# EntradaSensorTemperatura.net
KiCad netlist of a schematic drawn in Altium Designer
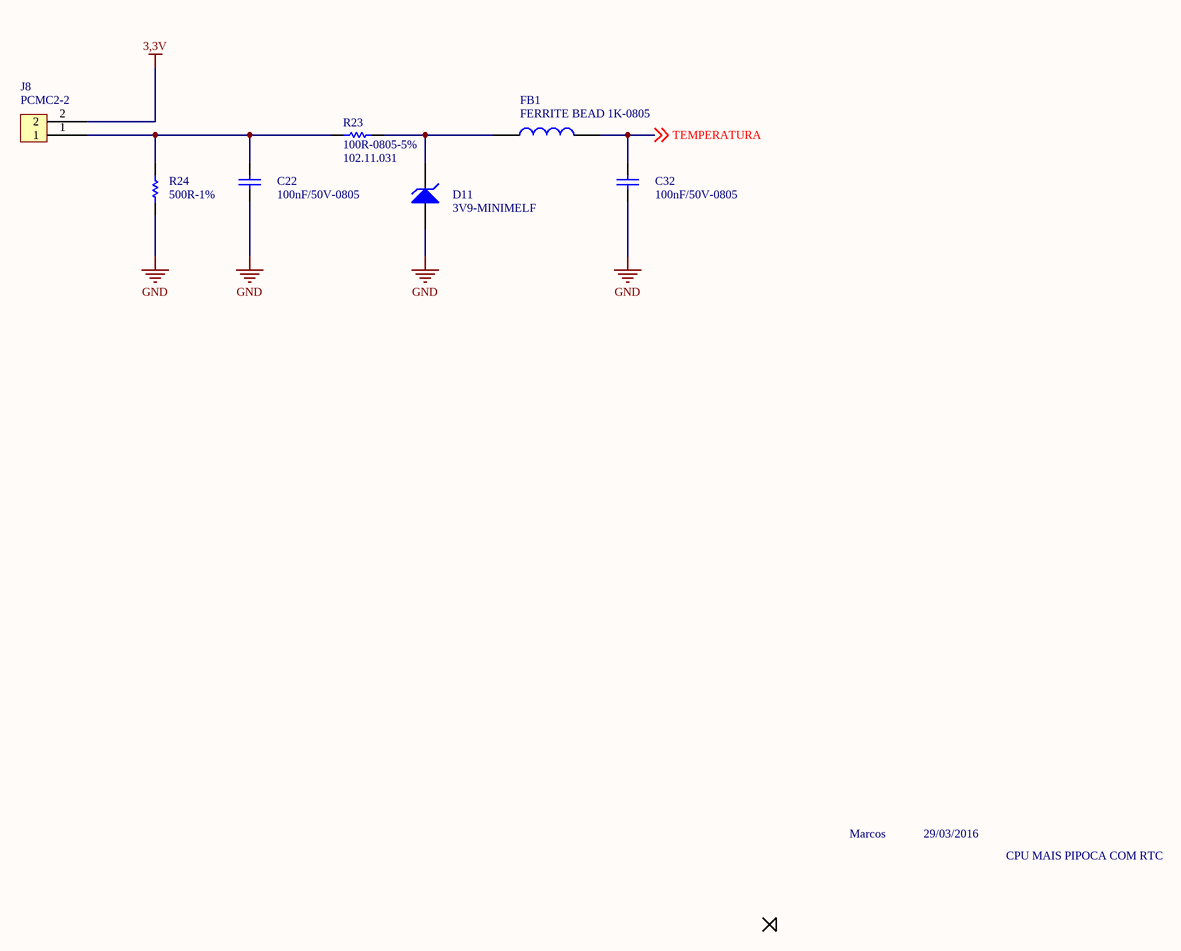
[diagram p0: EntradaSensorTemperatura.SchDoc]

(export (version "E")
  (design (tool "Eeschema 10.0.6"))
  (components
    (comp (ref "C22")
      (value "100nF/50V-0805")
      (footprint "0805-REVISADO O")
      (description "100nF/50-0805-NPO")
      (libsource (lib "AquinoLib") (part "100nF/50-0805-NPO"))
    )
    (comp (ref "C32")
      (value "100nF/50V-0805")
      (footprint "0805-REVISADO O")
      (description "100nF/50-0805-NPO")
      (libsource (lib "AquinoLib") (part "100nF/50-0805-NPO"))
    )
    (comp (ref "D11")
      (value "3V9-MINIMELF")
      (footprint "MINIMLEF/SOD80")
      (description "3V3-SOD80-1/2W")
      (libsource (lib "AquinoLib") (part "ZENER 3V3-SOD80"))
    )
    (comp (ref "FB1")
      (value "FERRITE BEAD 1K-0805")
      (footprint "0805-REVISADO O")
      (libsource (lib "AquinoLib") (part "FERRITE BEAD 1K-0805"))
    )
    (comp (ref "J8") (value "PCMC2-2") (footprint "PCMC2-2") (libsource (lib "AquinoLib") (part "PCMC2-2")))
    (comp (ref "R23")
      (value "100R-0805-5%")
      (footprint "0805-REVISADO O")
      (fields (field (name "ERP") "102.11.031"))
      (libsource (lib "AquinoLib") (part "100R-0805-5%"))
    )
    (comp (ref "R24")
      (value "500R-1%")
      (footprint "0805-REVISADO O")
      (description "10K-0805-5%")
      (libsource (lib "AquinoLib") (part "10K-0805-5%"))
    )
  )
  (nets
    (net (code "1") (name "3,3V") (class "Default")
      (node (ref "J8") (pin "2") (pinfunction "2_2") (pintype "passive"))
    )
    (net (code "2") (name "GND") (class "Default")
      (node (ref "C22") (pin "1") (pinfunction "1_1") (pintype "passive"))
      (node (ref "C32") (pin "1") (pinfunction "1_1") (pintype "passive"))
      (node (ref "D11") (pin "1") (pinfunction "A_1") (pintype "passive"))
      (node (ref "R24") (pin "1") (pinfunction "1_1") (pintype "passive"))
    )
    (net (code "3") (name "Net-(C22-Pad2)") (class "Default")
      (node (ref "C22") (pin "2") (pinfunction "2_2") (pintype "passive"))
      (node (ref "J8") (pin "1") (pinfunction "1_1") (pintype "passive"))
      (node (ref "R23") (pin "1") (pinfunction "1_1") (pintype "passive"))
      (node (ref "R24") (pin "2") (pinfunction "2_2") (pintype "passive"))
    )
    (net (code "4") (name "Net-(D11-K)") (class "Default")
      (node (ref "D11") (pin "2") (pinfunction "K_2") (pintype "passive"))
      (node (ref "FB1") (pin "1") (pinfunction "1_1") (pintype "passive"))
      (node (ref "R23") (pin "2") (pinfunction "2_2") (pintype "passive"))
    )
    (net (code "5") (name "TEMPERATURA") (class "Default")
      (node (ref "C32") (pin "2") (pinfunction "2_2") (pintype "passive"))
      (node (ref "FB1") (pin "2") (pinfunction "2_2") (pintype "passive"))
    )
  )
)
